# Pre-CHG_switch.net
KiCad netlist of a schematic drawn in Altium Designer
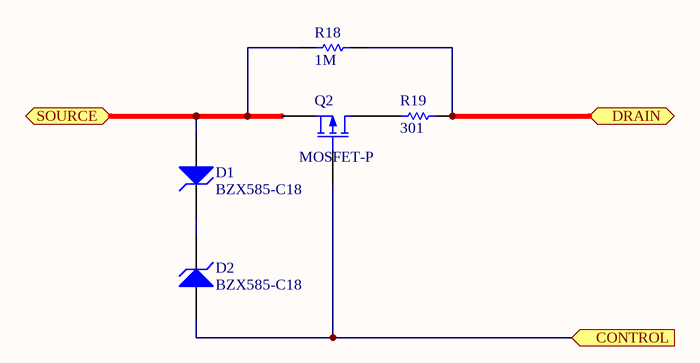
[diagram p0: Pre-CHG_switch.SchDoc]

(export (version "E")
  (design (tool "Eeschema 10.0.6"))
  (components
    (comp (ref "D1")
      (value "BZX585-C18")
      (footprint "DIODE-0.7")
      (description "Zener Diode")
      (fields (field (name "PUBLISHER") "Altium Limited"))
      (libsource (lib "Miscellaneous Devices") (part "D Zener"))
    )
    (comp (ref "D2")
      (value "BZX585-C18")
      (footprint "DIODE-0.7")
      (description "Zener Diode")
      (fields (field (name "PUBLISHER") "Altium Limited"))
      (libsource (lib "Miscellaneous Devices") (part "D Zener"))
    )
    (comp (ref "Q2")
      (value "MOSFET-P")
      (footprint "E3")
      (description "SI4435DDY")
      (fields (field (name "PUBLISHER") "Altium Limited"))
      (libsource (lib "Miscellaneous Devices") (part "MOSFET-P"))
    )
    (comp (ref "R18")
      (value "1M")
      (footprint "AXIAL-0.3")
      (description "Resistor")
      (fields (field (name "PUBLISHER") "Altium Limited"))
      (libsource (lib "Miscellaneous Devices") (part "Res1"))
    )
    (comp (ref "R19")
      (value "301")
      (footprint "AXIAL-0.3")
      (description "Resistor 1W")
      (fields (field (name "PUBLISHER") "Altium Limited"))
      (libsource (lib "Miscellaneous Devices") (part "Res1"))
    )
  )
  (nets
    (net (code "1") (name "/CONTROL") (class "Default")
      (node (ref "D2") (pin "1") (pinfunction "A_1") (pintype "passive"))
      (node (ref "Q2") (pin "2") (pinfunction "G_2") (pintype "passive"))
    )
    (net (code "2") (name "/DRAIN") (class "Default")
      (node (ref "R18") (pin "2") (pinfunction "2_2") (pintype "passive"))
      (node (ref "R19") (pin "2") (pinfunction "2_2") (pintype "passive"))
    )
    (net (code "3") (name "/SOURCE") (class "Default")
      (node (ref "D1") (pin "1") (pinfunction "A_1") (pintype "passive"))
      (node (ref "Q2") (pin "3") (pinfunction "S_3") (pintype "passive"))
      (node (ref "R18") (pin "1") (pinfunction "1_1") (pintype "passive"))
    )
    (net (code "4") (name "Net-(D1-K)") (class "Default")
      (node (ref "D1") (pin "2") (pinfunction "K_2") (pintype "passive"))
      (node (ref "D2") (pin "2") (pinfunction "K_2") (pintype "passive"))
    )
    (net (code "5") (name "Net-(Q2-D)") (class "Default")
      (node (ref "Q2") (pin "1") (pinfunction "D_1") (pintype "passive"))
      (node (ref "R19") (pin "1") (pinfunction "1_1") (pintype "passive"))
    )
  )
)
